# analog-in.net
KiCad netlist of a schematic drawn in EAGLE
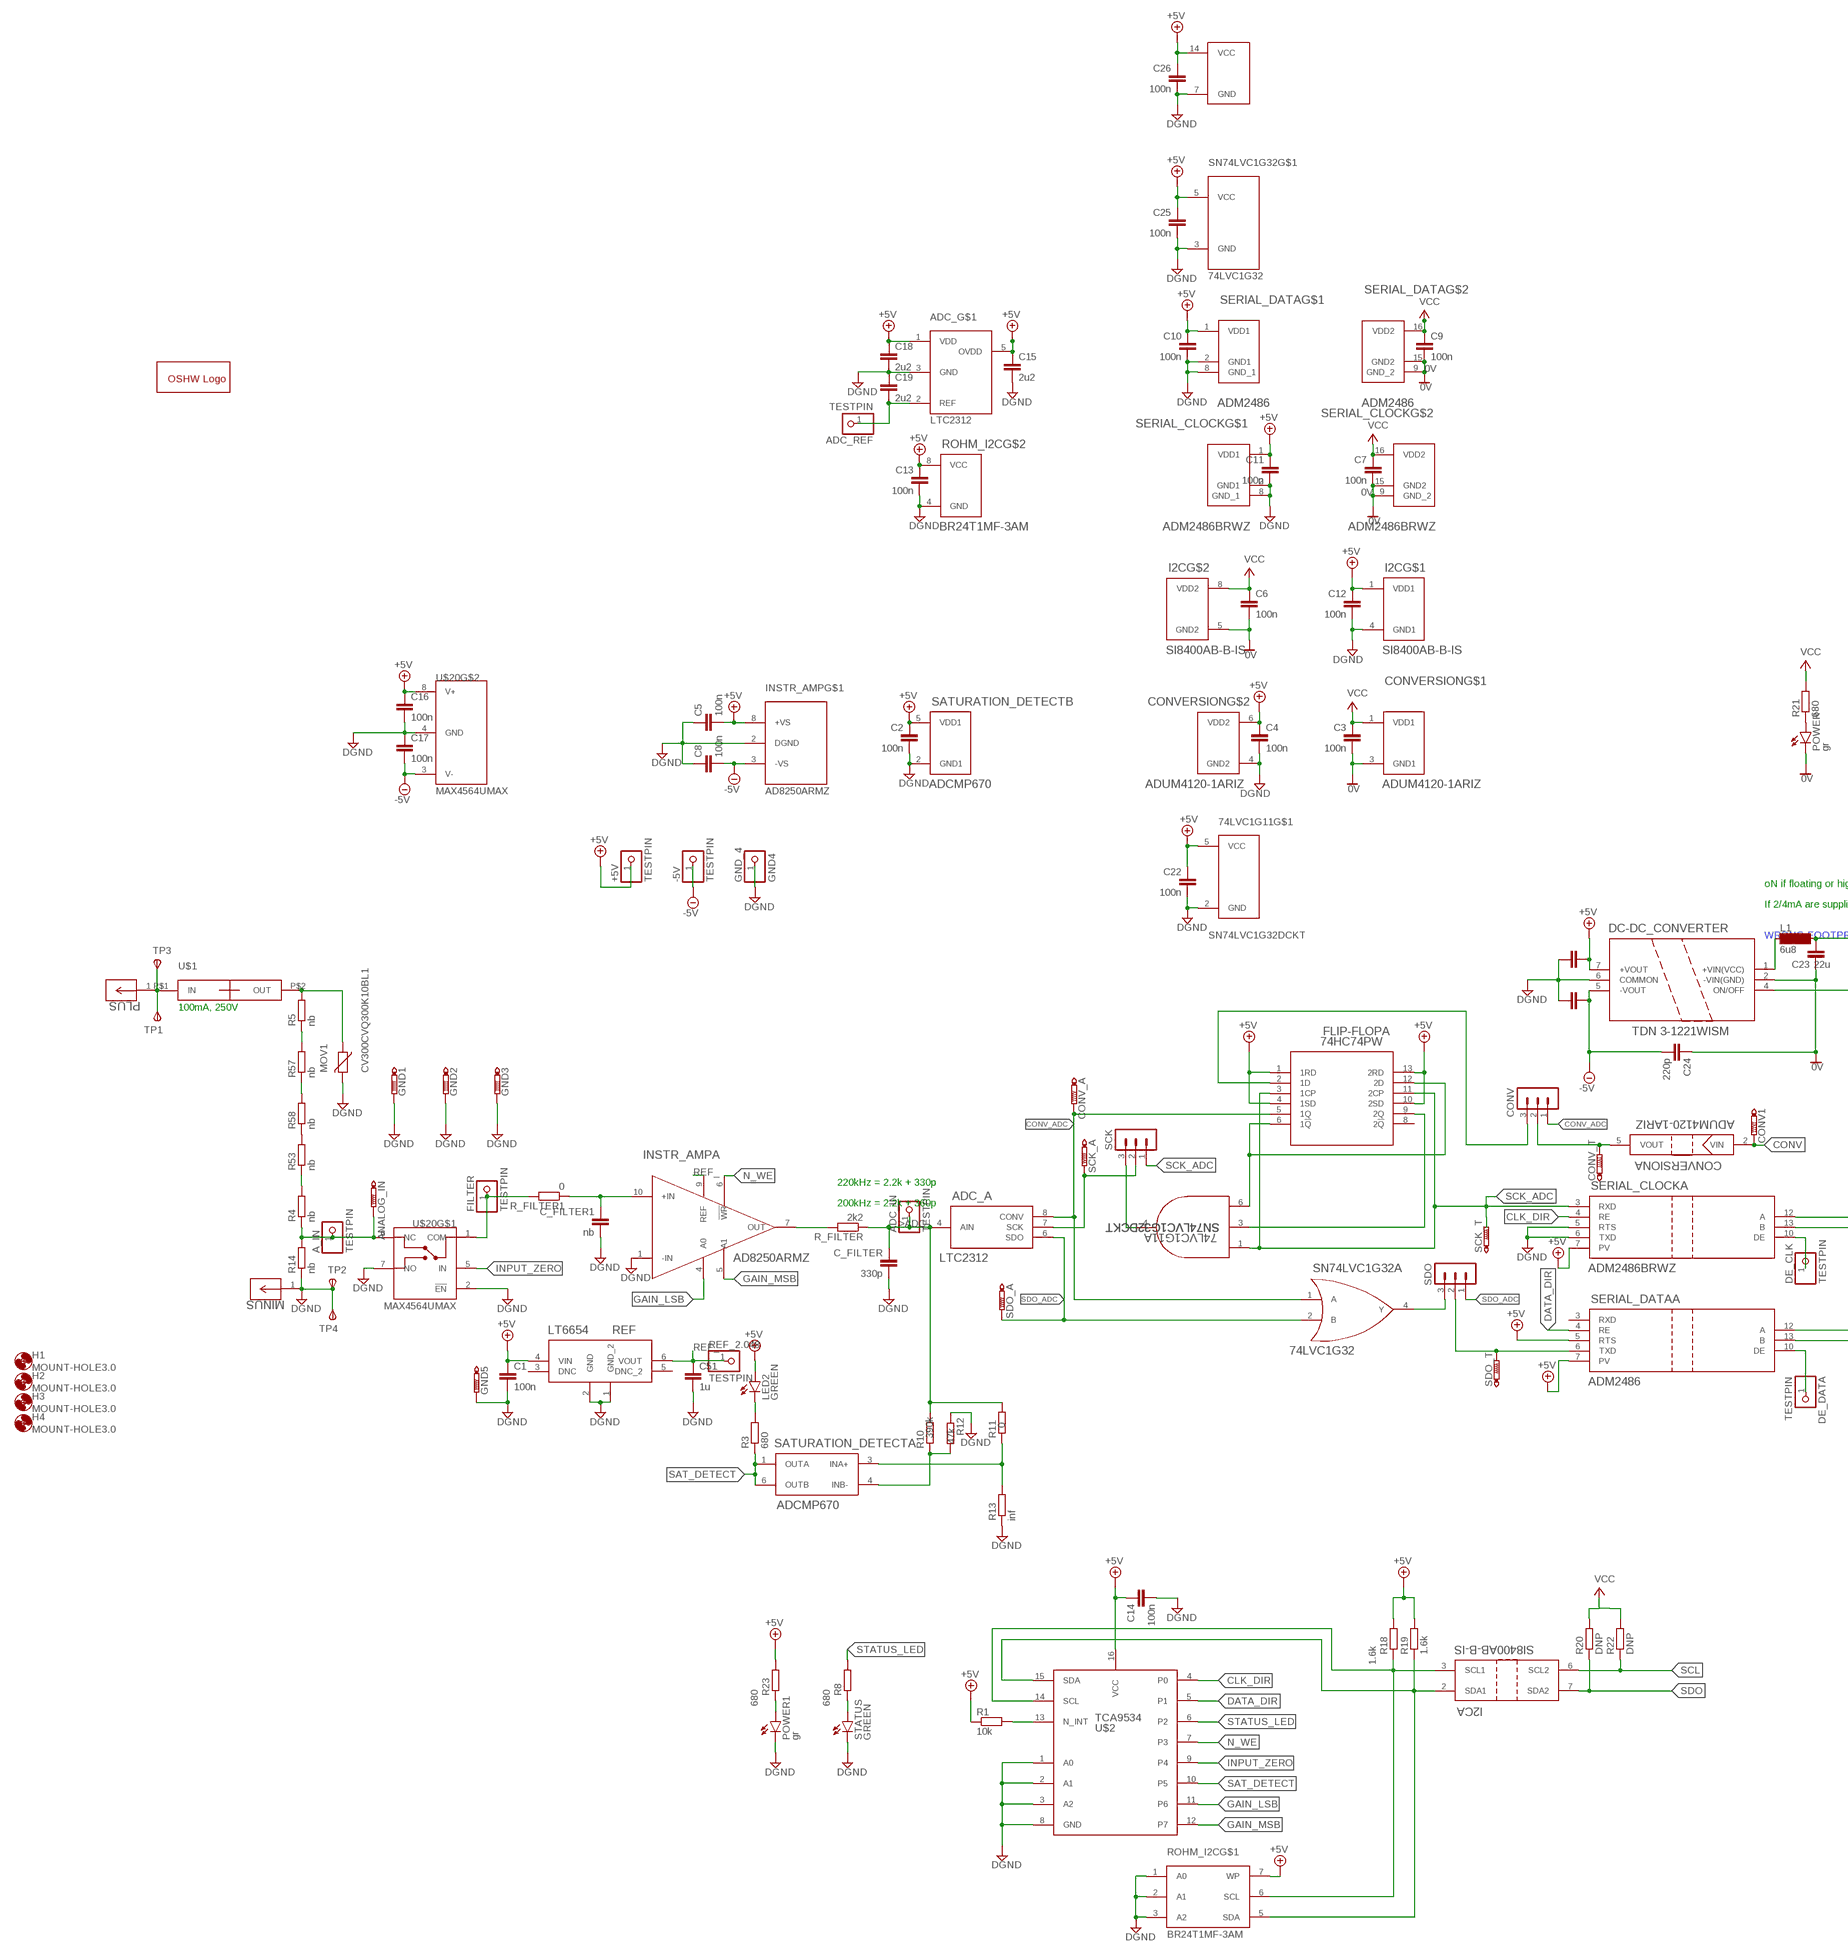
[diagram p0: schematic, sheet 1, part 1 of 2]
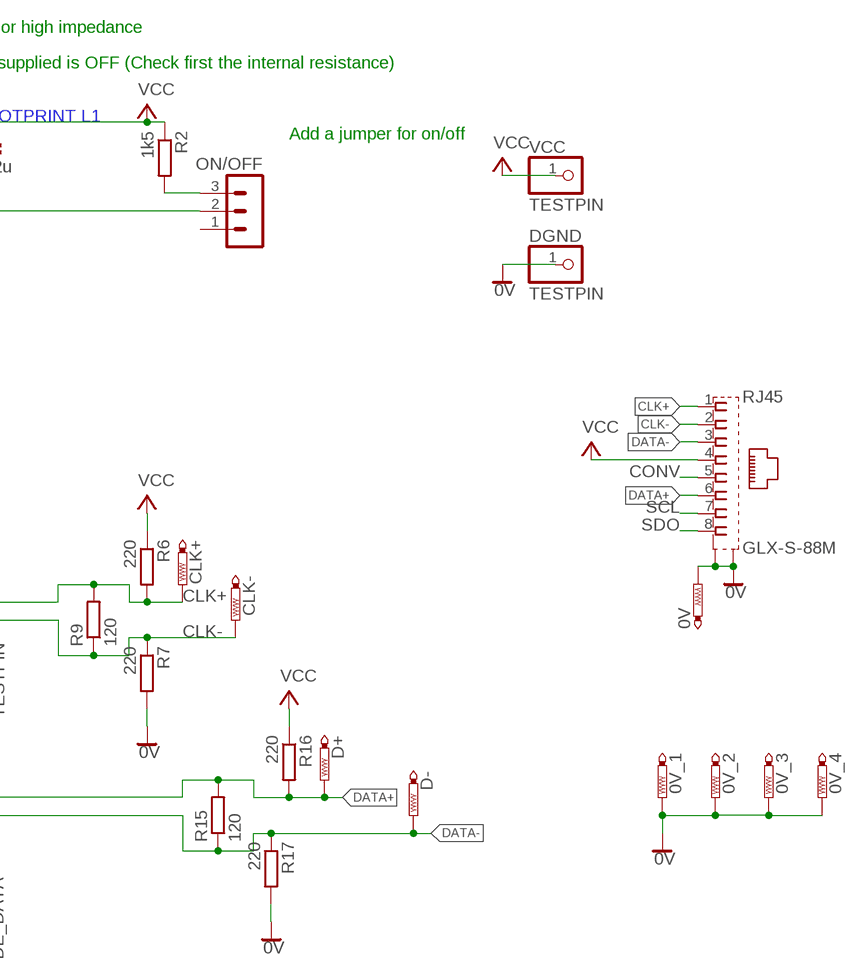
[diagram p1: schematic, sheet 1, part 2 of 2]

(export (version "E")
  (design (tool "Eeschema 10.0.6"))
  (components
    (comp (ref "+5V")
      (value "TESTPIN")
      (footprint "eagle-import:1X01")
      (libsource (lib "eagle-import") (part "TESTPIN"))
    )
    (comp (ref "-5V")
      (value "TESTPIN")
      (footprint "eagle-import:1X01")
      (libsource (lib "eagle-import") (part "TESTPIN"))
    )
    (comp (ref "0V")
      (value "PTR1B1,27")
      (footprint "eagle-import:B1,27")
      (libsource (lib "eagle-import") (part "PTR1B1,27"))
    )
    (comp (ref "0V_1")
      (value "PTR1B1,27")
      (footprint "eagle-import:B1,27")
      (libsource (lib "eagle-import") (part "PTR1B1,27"))
    )
    (comp (ref "0V_2")
      (value "PTR1B1,27")
      (footprint "eagle-import:B1,27")
      (libsource (lib "eagle-import") (part "PTR1B1,27"))
    )
    (comp (ref "0V_3")
      (value "PTR1B1,27")
      (footprint "eagle-import:B1,27")
      (libsource (lib "eagle-import") (part "PTR1B1,27"))
    )
    (comp (ref "0V_4")
      (value "PTR1B1,27")
      (footprint "eagle-import:B1,27")
      (libsource (lib "eagle-import") (part "PTR1B1,27"))
    )
    (comp (ref "74LVC1G11")
      (value "SN74LVC1G32DCKT")
      (footprint "eagle-import:DBV0006A_L")
      (fields (field (name "MANUFACTURER") "Texas Instruments") (field (name "PARTNUMBER") "SN74LVC1G11DBVR"))
      (libsource (lib "eagle-import") (part "SN74LVC1G11DBVRDBV0006A_L"))
    )
    (comp (ref "ADC_")
      (value "LTC2312")
      (footprint "eagle-import:TSOT-23_TS8_LIT")
      (fields
        (field (name "MANUFACTURER_PART_NUMBER") "LTC2312ITS8-14#TRMPBF")
        (field (name "DIGIKEY") "LTC2312CTS8-14#TRMPBFTR-ND")
      )
      (libsource (lib "eagle-import") (part "LTC2312ITS8-14TRMPBF"))
    )
    (comp (ref "ADC_IN")
      (value "TESTPIN")
      (footprint "eagle-import:1X01")
      (libsource (lib "eagle-import") (part "TESTPIN"))
    )
    (comp (ref "ADC_REF")
      (value "TESTPIN")
      (footprint "eagle-import:1X01")
      (libsource (lib "eagle-import") (part "TESTPIN"))
    )
    (comp (ref "ANALOG_IN")
      (value "PTR1B1,27")
      (footprint "eagle-import:B1,27")
      (libsource (lib "eagle-import") (part "PTR1B1,27"))
    )
    (comp (ref "A_IN")
      (value "TESTPIN")
      (footprint "eagle-import:1X01")
      (libsource (lib "eagle-import") (part "TESTPIN"))
    )
    (comp (ref "C1")
      (value "100n")
      (footprint "eagle-import:C0805")
      (libsource (lib "eagle-import") (part "C-EUC0805"))
    )
    (comp (ref "C2")
      (value "100n")
      (footprint "eagle-import:C0805K")
      (libsource (lib "eagle-import") (part "C-EUC0805K"))
    )
    (comp (ref "C3")
      (value "100n")
      (footprint "eagle-import:C0805K")
      (libsource (lib "eagle-import") (part "C-EUC0805K"))
    )
    (comp (ref "C4")
      (value "100n")
      (footprint "eagle-import:C0805K")
      (libsource (lib "eagle-import") (part "C-EUC0805K"))
    )
    (comp (ref "C5")
      (value "100n")
      (footprint "eagle-import:C0805K")
      (libsource (lib "eagle-import") (part "C-EUC0805K"))
    )
    (comp (ref "C6")
      (value "100n")
      (footprint "eagle-import:C0805K")
      (libsource (lib "eagle-import") (part "C-EUC0805K"))
    )
    (comp (ref "C7")
      (value "100n")
      (footprint "eagle-import:C0805K")
      (libsource (lib "eagle-import") (part "C-EUC0805K"))
    )
    (comp (ref "C8")
      (value "100n")
      (footprint "eagle-import:C0805K")
      (libsource (lib "eagle-import") (part "C-EUC0805K"))
    )
    (comp (ref "C9")
      (value "100n")
      (footprint "eagle-import:C0805K")
      (libsource (lib "eagle-import") (part "C-EUC0805K"))
    )
    (comp (ref "C10")
      (value "100n")
      (footprint "eagle-import:C0805K")
      (libsource (lib "eagle-import") (part "C-EUC0805K"))
    )
    (comp (ref "C11")
      (value "100n")
      (footprint "eagle-import:C0805K")
      (libsource (lib "eagle-import") (part "C-EUC0805K"))
    )
    (comp (ref "C12")
      (value "100n")
      (footprint "eagle-import:C0805K")
      (libsource (lib "eagle-import") (part "C-EUC0805K"))
    )
    (comp (ref "C13")
      (value "100n")
      (footprint "eagle-import:C0805K")
      (libsource (lib "eagle-import") (part "C-EUC0805K"))
    )
    (comp (ref "C14")
      (value "100n")
      (footprint "eagle-import:C0805K")
      (libsource (lib "eagle-import") (part "C-EUC0805K"))
    )
    (comp (ref "C15")
      (value "2u2")
      (footprint "eagle-import:C0805K")
      (libsource (lib "eagle-import") (part "C-EUC0805K"))
    )
    (comp (ref "C16")
      (value "100n")
      (footprint "eagle-import:C0805K")
      (libsource (lib "eagle-import") (part "C-EUC0805K"))
    )
    (comp (ref "C17")
      (value "100n")
      (footprint "eagle-import:C0805K")
      (libsource (lib "eagle-import") (part "C-EUC0805K"))
    )
    (comp (ref "C18")
      (value "2u2")
      (footprint "eagle-import:C0805K")
      (libsource (lib "eagle-import") (part "C-EUC0805K"))
    )
    (comp (ref "C19")
      (value "2u2")
      (footprint "eagle-import:C0805K")
      (libsource (lib "eagle-import") (part "C-EUC0805K"))
    )
    (comp (ref "C20")
      (value "100n")
      (footprint "eagle-import:C0805K")
      (libsource (lib "eagle-import") (part "C-EUC0805K"))
    )
    (comp (ref "C21")
      (value "100n")
      (footprint "eagle-import:C0805K")
      (libsource (lib "eagle-import") (part "C-EUC0805K"))
    )
    (comp (ref "C22")
      (value "100n")
      (footprint "eagle-import:C0805K")
      (libsource (lib "eagle-import") (part "C-EUC0805K"))
    )
    (comp (ref "C23")
      (value "22u")
      (footprint "eagle-import:C1206")
      (libsource (lib "eagle-import") (part "C-EUC1206"))
    )
    (comp (ref "C24")
      (value "220p")
      (footprint "eagle-import:C1808")
      (libsource (lib "eagle-import") (part "C-EUC1808"))
    )
    (comp (ref "C25")
      (value "100n")
      (footprint "eagle-import:C0805K")
      (libsource (lib "eagle-import") (part "C-EUC0805K"))
    )
    (comp (ref "C26")
      (value "100n")
      (footprint "eagle-import:C0805K")
      (libsource (lib "eagle-import") (part "C-EUC0805K"))
    )
    (comp (ref "C51")
      (value "1u")
      (footprint "eagle-import:C0805")
      (libsource (lib "eagle-import") (part "C-EUC0805"))
    )
    (comp (ref "CLK+")
      (value "PTR1B1,27")
      (footprint "eagle-import:B1,27")
      (libsource (lib "eagle-import") (part "PTR1B1,27"))
    )
    (comp (ref "CLK-")
      (value "PTR1B1,27")
      (footprint "eagle-import:B1,27")
      (libsource (lib "eagle-import") (part "PTR1B1,27"))
    )
    (comp (ref "CONV")
      (value "MA03-1")
      (footprint "eagle-import:MA03-1")
      (libsource (lib "eagle-import") (part "MA03-1"))
    )
    (comp (ref "CONV1")
      (value "PTR1B1,27")
      (footprint "eagle-import:B1,27")
      (libsource (lib "eagle-import") (part "PTR1B1,27"))
    )
    (comp (ref "CONVERSION")
      (value "ADUM4120-1ARIZ")
      (footprint "eagle-import:RI_6_1_ADI")
      (fields (field (name "DIGIKEY") "ADUM4120-1ARIZ-ND"))
      (libsource (lib "eagle-import") (part "ADUM4120-1ARIZ"))
    )
    (comp (ref "CONV_A")
      (value "PTR1B1,27")
      (footprint "eagle-import:B1,27")
      (libsource (lib "eagle-import") (part "PTR1B1,27"))
    )
    (comp (ref "CONV_T")
      (value "PTR1B1,27")
      (footprint "eagle-import:B1,27")
      (libsource (lib "eagle-import") (part "PTR1B1,27"))
    )
    (comp (ref "C_FILTER")
      (value "330p")
      (footprint "eagle-import:C0805K")
      (libsource (lib "eagle-import") (part "C-EUC0805K"))
    )
    (comp (ref "C_FILTER1")
      (value "nb")
      (footprint "eagle-import:C0805K")
      (libsource (lib "eagle-import") (part "C-EUC0805K"))
    )
    (comp (ref "D+")
      (value "PTR1B1,27")
      (footprint "eagle-import:B1,27")
      (libsource (lib "eagle-import") (part "PTR1B1,27"))
    )
    (comp (ref "D-")
      (value "PTR1B1,27")
      (footprint "eagle-import:B1,27")
      (libsource (lib "eagle-import") (part "PTR1B1,27"))
    )
    (comp (ref "DC-DC_CONVERTER")
      (value "TDN 3-1221WISM")
      (footprint "eagle-import:TDN3_TRP")
      (fields
        (field (name "MANUFACTURER_PART_NUMBER") "TDN 3-1211WI")
        (field (name "MANUFACTURER_PART_NUMBER_1") "TDN 3-1221WISM")
        (field (name "COPYRIGHT") "Copyright (C) 2018 Accelerated Designs. All rights reserved")
      )
      (libsource (lib "eagle-import") (part "TDN_3-1211WI"))
    )
    (comp (ref "DE_CLK")
      (value "TESTPIN")
      (footprint "eagle-import:1X01")
      (libsource (lib "eagle-import") (part "TESTPIN"))
    )
    (comp (ref "DE_DATA")
      (value "TESTPIN")
      (footprint "eagle-import:1X01")
      (libsource (lib "eagle-import") (part "TESTPIN"))
    )
    (comp (ref "DGND")
      (value "TESTPIN")
      (footprint "eagle-import:1X01")
      (libsource (lib "eagle-import") (part "TESTPIN"))
    )
    (comp (ref "FILTER")
      (value "TESTPIN")
      (footprint "eagle-import:1X01")
      (libsource (lib "eagle-import") (part "TESTPIN"))
    )
    (comp (ref "FLIP-FLOP")
      (value "74HC74PW")
      (footprint "eagle-import:TSSOP14_SOT402-1_NEX")
      (fields
        (field (name "MANUFACTURER_PART_NUMBER") "74HC74PW-Q100,118")
        (field (name "DIGIKEY") "1727-4083-1-ND")
        (field (name "COPYRIGHT") "Copyright (C) 2018 Accelerated Designs. All rights reserved")
      )
      (libsource (lib "eagle-import") (part "74HC74PW-Q100,118"))
    )
    (comp (ref "GND1")
      (value "PTR1B1,27")
      (footprint "eagle-import:B1,27")
      (libsource (lib "eagle-import") (part "PTR1B1,27"))
    )
    (comp (ref "GND2")
      (value "PTR1B1,27")
      (footprint "eagle-import:B1,27")
      (libsource (lib "eagle-import") (part "PTR1B1,27"))
    )
    (comp (ref "GND3")
      (value "PTR1B1,27")
      (footprint "eagle-import:B1,27")
      (libsource (lib "eagle-import") (part "PTR1B1,27"))
    )
    (comp (ref "GND5")
      (value "PTR1B1,27")
      (footprint "eagle-import:B1,27")
      (libsource (lib "eagle-import") (part "PTR1B1,27"))
    )
    (comp (ref "GND_4")
      (value "GND4")
      (footprint "eagle-import:1X01")
      (libsource (lib "eagle-import") (part "TESTPIN"))
    )
    (comp (ref "GOLD_ORB_SM1")
      (value "OSHWLOGOLOGO8MM")
      (footprint "eagle-import:OSHW_8MM")
      (libsource (lib "eagle-import") (part "OSHWLOGOLOGO8MM"))
    )
    (comp (ref "H1")
      (value "MOUNT-HOLE3.0")
      (footprint "eagle-import:3,0")
      (libsource (lib "eagle-import") (part "MOUNT-HOLE3.0"))
    )
    (comp (ref "H2")
      (value "MOUNT-HOLE3.0")
      (footprint "eagle-import:3,0")
      (libsource (lib "eagle-import") (part "MOUNT-HOLE3.0"))
    )
    (comp (ref "H3")
      (value "MOUNT-HOLE3.0")
      (footprint "eagle-import:3,0")
      (libsource (lib "eagle-import") (part "MOUNT-HOLE3.0"))
    )
    (comp (ref "H4")
      (value "MOUNT-HOLE3.0")
      (footprint "eagle-import:3,0")
      (libsource (lib "eagle-import") (part "MOUNT-HOLE3.0"))
    )
    (comp (ref "I2C")
      (value "SI8400AB-B-IS")
      (footprint "eagle-import:R_8_ADI")
      (fields
        (field (name "MANUFACTURER_PART_NUMBER") "ADUM1251WARZ")
        (field (name "DIGIKEY") "ADUM1251ARZ-RL7TR-ND")
        (field (name "COPYRIGHT") "Copyright (C) 2018 Accelerated Designs. All rights reserved")
      )
      (libsource (lib "eagle-import") (part "ADUM1251WARZ"))
    )
    (comp (ref "INSTR_AMP")
      (value "AD8250ARMZ")
      (footprint "eagle-import:RM_10_ADI")
      (fields (field (name "DIGIKEY") "AD8250ARMZ-R7TR-ND"))
      (libsource (lib "eagle-import") (part "AD8250ARMZ"))
    )
    (comp (ref "L1")
      (value "6u8")
      (footprint "eagle-import:SM-NE29")
      (libsource (lib "eagle-import") (part "SM-NE29"))
    )
    (comp (ref "LED2")
      (value "GREEN")
      (footprint "eagle-import:SML0805")
      (libsource (lib "eagle-import") (part "LEDSML0805"))
    )
    (comp (ref "MINUS")
      (value "23.3200-21")
      (footprint "eagle-import:CONN_23.3200-21_SBI")
      (fields (field (name "COPYRIGHT") "Copyright (C) 2018 Accelerated Designs. All rights reserved"))
      (libsource (lib "eagle-import") (part "23.3200-21"))
    )
    (comp (ref "MOV1")
      (value "CV300CVQ300K10BL1")
      (footprint "eagle-import:CVQ300K10")
      (libsource (lib "eagle-import") (part "CV300CVQ300K10BL1"))
    )
    (comp (ref "ON/OFF")
      (value "MA03-1")
      (footprint "eagle-import:MA03-1")
      (libsource (lib "eagle-import") (part "MA03-1"))
    )
    (comp (ref "PLUS")
      (value "23.3200-21")
      (footprint "eagle-import:CONN_23.3200-21_SBI")
      (fields (field (name "COPYRIGHT") "Copyright (C) 2018 Accelerated Designs. All rights reserved"))
      (libsource (lib "eagle-import") (part "23.3200-21"))
    )
    (comp (ref "POWER")
      (value "gr")
      (footprint "eagle-import:SML0805")
      (libsource (lib "eagle-import") (part "LEDSML0805"))
    )
    (comp (ref "POWER1")
      (value "gr")
      (footprint "eagle-import:SML0805")
      (libsource (lib "eagle-import") (part "LEDSML0805"))
    )
    (comp (ref "R1")
      (value "10k")
      (footprint "eagle-import:R0805")
      (libsource (lib "eagle-import") (part "R-EU_R0805"))
    )
    (comp (ref "R2")
      (value "1k5")
      (footprint "eagle-import:R0805")
      (libsource (lib "eagle-import") (part "R-EU_R0805"))
    )
    (comp (ref "R3")
      (value "680")
      (footprint "eagle-import:R0805")
      (libsource (lib "eagle-import") (part "R-EU_R0805"))
    )
    (comp (ref "R4")
      (value "nb")
      (footprint "eagle-import:R1206")
      (libsource (lib "eagle-import") (part "R-EU_R1206"))
    )
    (comp (ref "R5")
      (value "nb")
      (footprint "eagle-import:R1206")
      (libsource (lib "eagle-import") (part "R-EU_R1206"))
    )
    (comp (ref "R6")
      (value "220")
      (footprint "eagle-import:R0805")
      (libsource (lib "eagle-import") (part "R-EU_R0805"))
    )
    (comp (ref "R7")
      (value "220")
      (footprint "eagle-import:R0805")
      (libsource (lib "eagle-import") (part "R-EU_R0805"))
    )
    (comp (ref "R8")
      (value "680")
      (footprint "eagle-import:R0805")
      (libsource (lib "eagle-import") (part "resistor_348_R-EU_R0805"))
    )
    (comp (ref "R9")
      (value "120")
      (footprint "eagle-import:R0805")
      (libsource (lib "eagle-import") (part "R-EU_R0805"))
    )
    (comp (ref "R10")
      (value "390k")
      (footprint "eagle-import:R0805")
      (libsource (lib "eagle-import") (part "R-EU_R0805"))
    )
    (comp (ref "R11")
      (value "0")
      (footprint "eagle-import:R0805")
      (libsource (lib "eagle-import") (part "R-EU_R0805"))
    )
    (comp (ref "R12")
      (value "47k")
      (footprint "eagle-import:R0805")
      (libsource (lib "eagle-import") (part "R-EU_R0805"))
    )
    (comp (ref "R13")
      (value "inf")
      (footprint "eagle-import:R0805")
      (libsource (lib "eagle-import") (part "R-EU_R0805"))
    )
    (comp (ref "R14")
      (value "nb")
      (footprint "eagle-import:R0805")
      (libsource (lib "eagle-import") (part "R-EU_R0805"))
    )
    (comp (ref "R15")
      (value "120")
      (footprint "eagle-import:R0805")
      (libsource (lib "eagle-import") (part "R-EU_R0805"))
    )
    (comp (ref "R16")
      (value "220")
      (footprint "eagle-import:R0805")
      (libsource (lib "eagle-import") (part "R-EU_R0805"))
    )
    (comp (ref "R17")
      (value "220")
      (footprint "eagle-import:R0805")
      (libsource (lib "eagle-import") (part "R-EU_R0805"))
    )
    (comp (ref "R18")
      (value "1.6k")
      (footprint "eagle-import:R0805")
      (libsource (lib "eagle-import") (part "resistor_348_R-EU_R0805"))
    )
    (comp (ref "R19")
      (value "1.6k")
      (footprint "eagle-import:R0805")
      (libsource (lib "eagle-import") (part "resistor_348_R-EU_R0805"))
    )
    (comp (ref "R20")
      (value "DNP")
      (footprint "eagle-import:R0805")
      (libsource (lib "eagle-import") (part "resistor_348_R-EU_R0805"))
    )
    (comp (ref "R21")
      (value "680")
      (footprint "eagle-import:R0805")
      (libsource (lib "eagle-import") (part "R-EU_R0805"))
    )
    (comp (ref "R22")
      (value "DNP")
      (footprint "eagle-import:R0805")
      (libsource (lib "eagle-import") (part "resistor_348_R-EU_R0805"))
    )
    (comp (ref "R23")
      (value "680")
      (footprint "eagle-import:R0805")
      (libsource (lib "eagle-import") (part "resistor_348_R-EU_R0805"))
    )
    (comp (ref "R53")
      (value "nb")
      (footprint "eagle-import:R1206")
      (libsource (lib "eagle-import") (part "R-EU_R1206"))
    )
    (comp (ref "R57")
      (value "nb")
      (footprint "eagle-import:R1206")
      (libsource (lib "eagle-import") (part "R-EU_R1206"))
    )
    (comp (ref "R58")
      (value "nb")
      (footprint "eagle-import:R1206")
      (libsource (lib "eagle-import") (part "R-EU_R1206"))
    )
    (comp (ref "REF")
      (value "LT6654")
      (footprint "eagle-import:S_6_ADI")
      (fields
        (field (name "MANUFACTURER_PART_NUMBER") "LT6654AIS6-2.048#TRMPBF")
        (field (name "COPYRIGHT") "Copyright (C) 2016 Accelerated Designs. All rights reserved")
      )
      (libsource (lib "eagle-import") (part "LT6654AIS6-2.048TRMPBF"))
    )
    (comp (ref "REF_2.048")
      (value "TESTPIN")
      (footprint "eagle-import:1X01")
      (libsource (lib "eagle-import") (part "TESTPIN"))
    )
    (comp (ref "RJ45")
      (value "GLX-S-88M")
      (footprint "eagle-import:GLX-S-88M")
      (libsource (lib "eagle-import") (part "GLX-S-88M"))
    )
    (comp (ref "ROHM_I2C")
      (value "BR24T1MF-3AM")
      (footprint "eagle-import:BR24T1MFJ-3AM")
      (fields (field (name "DIGIKEY") "BR24T1MF-3AME2TR-ND"))
      (libsource (lib "eagle-import") (part "BR24T1MF-3AM"))
    )
    (comp (ref "R_FILTER")
      (value "2k2")
      (footprint "eagle-import:R0805")
      (libsource (lib "eagle-import") (part "R-EU_R0805"))
    )
    (comp (ref "R_FILTER1")
      (value "0")
      (footprint "eagle-import:R0805")
      (libsource (lib "eagle-import") (part "R-EU_R0805"))
    )
    (comp (ref "SATURATION_DETECT")
      (value "ADCMP670")
      (footprint "eagle-import:UJ_6_ADI")
      (fields
        (field (name "MANUFACTURER_PART_NUMBER") "ADCMP670-1YUJZ-RL7")
        (field (name "DIGIKEY") "ADCMP670-1YUJZ-RL7TR-ND")
      )
      (libsource (lib "eagle-import") (part "ADCMP670-1YUJZ-RL7"))
    )
    (comp (ref "SCK")
      (value "MA03-1")
      (footprint "eagle-import:MA03-1")
      (libsource (lib "eagle-import") (part "MA03-1"))
    )
    (comp (ref "SCK_A")
      (value "PTR1B1,27")
      (footprint "eagle-import:B1,27")
      (libsource (lib "eagle-import") (part "PTR1B1,27"))
    )
    (comp (ref "SCK_T")
      (value "PTR1B1,27")
      (footprint "eagle-import:B1,27")
      (libsource (lib "eagle-import") (part "PTR1B1,27"))
    )
    (comp (ref "SDO")
      (value "MA03-1")
      (footprint "eagle-import:MA03-1")
      (libsource (lib "eagle-import") (part "MA03-1"))
    )
    (comp (ref "SDO_A")
      (value "PTR1B1,27")
      (footprint "eagle-import:B1,27")
      (libsource (lib "eagle-import") (part "PTR1B1,27"))
    )
    (comp (ref "SDO_T")
      (value "PTR1B1,27")
      (footprint "eagle-import:B1,27")
      (libsource (lib "eagle-import") (part "PTR1B1,27"))
    )
    (comp (ref "SERIAL_CLOCK")
      (value "ADM2486BRWZ")
      (footprint "eagle-import:RW_16_ADI")
      (fields
        (field (name "MANUFACTURER_PART_NUMBER") "ADM2486BRWZ-REEL")
        (field (name "DIGIKEY") "ADM2486BRWZ-REELTR-ND")
      )
      (libsource (lib "eagle-import") (part "ADM2486BRWZ-REEL"))
    )
    (comp (ref "SERIAL_DATA")
      (value "ADM2486")
      (footprint "eagle-import:RW_16_ADI")
      (fields
        (field (name "MANUFACTURER_PART_NUMBER") "ADM2486BRWZ-REEL")
        (field (name "DIGIKEY") "ADM2486BRWZ-REELTR-ND")
      )
      (libsource (lib "eagle-import") (part "ADM2486BRWZ-REEL"))
    )
    (comp (ref "SN74LVC1G32")
      (value "74LVC1G32")
      (footprint "eagle-import:DCK5-M")
      (fields
        (field (name "GENERIC_PART_NUMBER") "SN74LVC1G32")
        (field (name "MANUFACTURER") "Texas Instruments")
        (field (name "MANUFACTURER_PART_NUMBER") "SN74LVC1G32DCKT")
      )
      (libsource (lib "eagle-import") (part "SN74LVC1G32DCKTDCK5-M"))
    )
    (comp (ref "STATUS")
      (value "GREEN")
      (footprint "eagle-import:CHIPLED_0805")
      (libsource (lib "eagle-import") (part "LEDCHIPLED_0805"))
    )
    (comp (ref "TP1")
      (value "TPSTP20SQ")
      (footprint "eagle-import:TP20SQ")
      (libsource (lib "eagle-import") (part "TPSTP20SQ"))
    )
    (comp (ref "TP2")
      (value "TPSTP20SQ")
      (footprint "eagle-import:TP20SQ")
      (libsource (lib "eagle-import") (part "TPSTP20SQ"))
    )
    (comp (ref "TP3")
      (value "TPSTP20SQ")
      (footprint "eagle-import:TP20SQ")
      (libsource (lib "eagle-import") (part "TPSTP20SQ"))
    )
    (comp (ref "TP4")
      (value "TPSTP20SQ")
      (footprint "eagle-import:TP20SQ")
      (libsource (lib "eagle-import") (part "TPSTP20SQ"))
    )
    (comp (ref "U$1")
      (value "0508.500MXEP")
      (footprint "eagle-import:0508.500MXEP")
      (libsource (lib "eagle-import") (part "0508.500MXEP"))
    )
    (comp (ref "U$2")
      (value "TCA9534")
      (footprint "eagle-import:TSSOP16L")
      (libsource (lib "eagle-import") (part "TCA9534"))
    )
    (comp (ref "U$20")
      (value "MAX4564UMAX")
      (footprint "eagle-import:UMAX8")
      (fields (field (name "DIGIKEY") "MAX4564EUA+TR-ND") (field (name "MOUSER") "700-MAX4564EUA "))
      (libsource (lib "eagle-import") (part "MAX4564UMAX"))
    )
    (comp (ref "VCC")
      (value "TESTPIN")
      (footprint "eagle-import:1X01")
      (libsource (lib "eagle-import") (part "TESTPIN"))
    )
  )
  (nets
    (net (code "1") (name "+5V") (class "Default")
      (node (ref "+5V") (pin "1") (pinfunction "1_1") (pintype "passive"))
      (node (ref "74LVC1G11") (pin "5") (pinfunction "VCC_5") (pintype "bidirectional"))
      (node (ref "ADC_") (pin "1") (pinfunction "VDD_1") (pintype "bidirectional"))
      (node (ref "ADC_") (pin "5") (pinfunction "OVDD_5") (pintype "bidirectional"))
      (node (ref "C1") (pin "1") (pinfunction "1_1") (pintype "passive"))
      (node (ref "C10") (pin "1") (pinfunction "1_1") (pintype "passive"))
      (node (ref "C11") (pin "1") (pinfunction "1_1") (pintype "passive"))
      (node (ref "C12") (pin "1") (pinfunction "1_1") (pintype "passive"))
      (node (ref "C13") (pin "1") (pinfunction "1_1") (pintype "passive"))
      (node (ref "C14") (pin "1") (pinfunction "1_1") (pintype "passive"))
      (node (ref "C15") (pin "1") (pinfunction "1_1") (pintype "passive"))
      (node (ref "C16") (pin "1") (pinfunction "1_1") (pintype "passive"))
      (node (ref "C18") (pin "1") (pinfunction "1_1") (pintype "passive"))
      (node (ref "C2") (pin "1") (pinfunction "1_1") (pintype "passive"))
      (node (ref "C20") (pin "2") (pinfunction "2_2") (pintype "passive"))
      (node (ref "C22") (pin "1") (pinfunction "1_1") (pintype "passive"))
      (node (ref "C25") (pin "1") (pinfunction "1_1") (pintype "passive"))
      (node (ref "C26") (pin "1") (pinfunction "1_1") (pintype "passive"))
      (node (ref "C4") (pin "1") (pinfunction "1_1") (pintype "passive"))
      (node (ref "C5") (pin "2") (pinfunction "2_2") (pintype "passive"))
      (node (ref "CONVERSION") (pin "6") (pinfunction "VDD2_6") (pintype "passive"))
      (node (ref "DC-DC_CONVERTER") (pin "7") (pinfunction "+VOUT_7") (pintype "output"))
      (node (ref "FLIP-FLOP") (pin "1") (pinfunction "1RD_1") (pintype "input"))
      (node (ref "FLIP-FLOP") (pin "10") (pinfunction "2SD_10") (pintype "input"))
      (node (ref "FLIP-FLOP") (pin "13") (pinfunction "2RD_13") (pintype "input"))
      (node (ref "FLIP-FLOP") (pin "14") (pinfunction "VCC_14") (pintype "power_in"))
      (node (ref "FLIP-FLOP") (pin "4") (pinfunction "1SD_4") (pintype "input"))
      (node (ref "I2C") (pin "1") (pinfunction "VDD1_1") (pintype "power_in"))
      (node (ref "INSTR_AMP") (pin "8") (pinfunction "+VS_8") (pintype "bidirectional"))
      (node (ref "LED2") (pin "A") (pinfunction "A_A") (pintype "passive"))
      (node (ref "R1") (pin "1") (pinfunction "1_1") (pintype "passive"))
      (node (ref "R18") (pin "2") (pinfunction "2_2") (pintype "passive"))
      (node (ref "R19") (pin "2") (pinfunction "2_2") (pintype "passive"))
      (node (ref "R23") (pin "2") (pinfunction "2_2") (pintype "passive"))
      (node (ref "REF") (pin "4") (pinfunction "VIN_4") (pintype "input"))
      (node (ref "ROHM_I2C") (pin "7") (pinfunction "WP_7") (pintype "input"))
      (node (ref "ROHM_I2C") (pin "8") (pinfunction "VCC_8") (pintype "passive"))
      (node (ref "SATURATION_DETECT") (pin "5") (pinfunction "VDD1_5") (pintype "passive"))
      (node (ref "SERIAL_CLOCK") (pin "1") (pinfunction "VDD1_1") (pintype "power_in"))
      (node (ref "SERIAL_CLOCK") (pin "7") (pinfunction "PV_7") (pintype "passive"))
      (node (ref "SERIAL_DATA") (pin "1") (pinfunction "VDD1_1") (pintype "power_in"))
      (node (ref "SERIAL_DATA") (pin "5") (pinfunction "RTS_5") (pintype "passive"))
      (node (ref "SERIAL_DATA") (pin "7") (pinfunction "PV_7") (pintype "passive"))
      (node (ref "SN74LVC1G32") (pin "5") (pinfunction "VCC_5") (pintype "bidirectional"))
      (node (ref "U$2") (pin "16") (pinfunction "VCC_16") (pintype "bidirectional"))
      (node (ref "U$20") (pin "8") (pinfunction "V+_8") (pintype "bidirectional"))
    )
    (net (code "2") (name "-5V") (class "Default")
      (node (ref "-5V") (pin "1") (pinfunction "1_1") (pintype "passive"))
      (node (ref "C17") (pin "2") (pinfunction "2_2") (pintype "passive"))
      (node (ref "C21") (pin "2") (pinfunction "2_2") (pintype "passive"))
      (node (ref "C24") (pin "2") (pinfunction "2_2") (pintype "passive"))
      (node (ref "C8") (pin "2") (pinfunction "2_2") (pintype "passive"))
      (node (ref "DC-DC_CONVERTER") (pin "5") (pinfunction "-VOUT_5") (pintype "output"))
      (node (ref "INSTR_AMP") (pin "3") (pinfunction "-VS_3") (pintype "bidirectional"))
      (node (ref "U$20") (pin "3") (pinfunction "V-_3") (pintype "bidirectional"))
    )
    (net (code "3") (name "/>ADC") (class "Default")
      (node (ref "ADC_") (pin "4") (pinfunction "AIN_4") (pintype "input"))
      (node (ref "ADC_IN") (pin "1") (pinfunction "1_1") (pintype "passive"))
      (node (ref "C_FILTER") (pin "1") (pinfunction "1_1") (pintype "passive"))
      (node (ref "R10") (pin "2") (pinfunction "2_2") (pintype "passive"))
      (node (ref "R11") (pin "2") (pinfunction "2_2") (pintype "passive"))
      (node (ref "R_FILTER") (pin "1") (pinfunction "1_1") (pintype "passive"))
    )
    (net (code "4") (name "/REF_") (class "Default")
      (node (ref "C51") (pin "1") (pinfunction "1_1") (pintype "passive"))
      (node (ref "INSTR_AMP") (pin "9") (pinfunction "REF_9") (pintype "passive"))
      (node (ref "REF") (pin "6") (pinfunction "VOUT_6") (pintype "output"))
      (node (ref "REF_2.048") (pin "1") (pinfunction "1_1") (pintype "passive"))
    )
    (net (code "5") (name "0V") (class "Default")
      (node (ref "0V") (pin "TP") (pinfunction "TP_TP") (pintype "input"))
      (node (ref "0V_1") (pin "TP") (pinfunction "TP_TP") (pintype "input"))
      (node (ref "0V_2") (pin "TP") (pinfunction "TP_TP") (pintype "input"))
      (node (ref "0V_3") (pin "TP") (pinfunction "TP_TP") (pintype "input"))
      (node (ref "0V_4") (pin "TP") (pinfunction "TP_TP") (pintype "input"))
      (node (ref "C23") (pin "1") (pinfunction "1_1") (pintype "passive"))
      (node (ref "C24") (pin "1") (pinfunction "1_1") (pintype "passive"))
      (node (ref "C3") (pin "2") (pinfunction "2_2") (pintype "passive"))
      (node (ref "C6") (pin "2") (pinfunction "2_2") (pintype "passive"))
      (node (ref "C7") (pin "2") (pinfunction "2_2") (pintype "passive"))
      (node (ref "C9") (pin "2") (pinfunction "2_2") (pintype "passive"))
      (node (ref "CONVERSION") (pin "3") (pinfunction "GND1_3") (pintype "passive"))
      (node (ref "DC-DC_CONVERTER") (pin "2") (pinfunction "-VIN(GND)_2") (pintype "passive"))
      (node (ref "DGND") (pin "1") (pinfunction "1_1") (pintype "passive"))
      (node (ref "I2C") (pin "5") (pinfunction "GND2_5") (pintype "passive"))
      (node (ref "POWER") (pin "C") (pinfunction "C_C") (pintype "passive"))
      (node (ref "R17") (pin "2") (pinfunction "2_2") (pintype "passive"))
      (node (ref "R7") (pin "2") (pinfunction "2_2") (pintype "passive"))
      (node (ref "RJ45") (pin "S1") (pinfunction "S1_S1") (pintype "passive"))
      (node (ref "RJ45") (pin "S2") (pinfunction "S2_S2") (pintype "passive"))
      (node (ref "SERIAL_CLOCK") (pin "15") (pinfunction "GND2_15") (pintype "power_in"))
      (node (ref "SERIAL_CLOCK") (pin "9") (pinfunction "GND_2_9") (pintype "power_in"))
      (node (ref "SERIAL_DATA") (pin "15") (pinfunction "GND2_15") (pintype "power_in"))
      (node (ref "SERIAL_DATA") (pin "9") (pinfunction "GND_2_9") (pintype "power_in"))
    )
    (net (code "6") (name "CLK+") (class "Default")
      (node (ref "CLK+") (pin "TP") (pinfunction "TP_TP") (pintype "input"))
      (node (ref "R6") (pin "2") (pinfunction "2_2") (pintype "passive"))
      (node (ref "R9") (pin "2") (pinfunction "2_2") (pintype "passive"))
      (node (ref "RJ45") (pin "1") (pinfunction "1_1") (pintype "passive"))
      (node (ref "SERIAL_CLOCK") (pin "12") (pinfunction "A_12") (pintype "passive"))
    )
    (net (code "7") (name "CLK-") (class "Default")
      (node (ref "CLK-") (pin "TP") (pinfunction "TP_TP") (pintype "input"))
      (node (ref "R7") (pin "1") (pinfunction "1_1") (pintype "passive"))
      (node (ref "R9") (pin "1") (pinfunction "1_1") (pintype "passive"))
      (node (ref "RJ45") (pin "2") (pinfunction "2_2") (pintype "passive"))
      (node (ref "SERIAL_CLOCK") (pin "13") (pinfunction "B_13") (pintype "passive"))
    )
    (net (code "8") (name "CLK_DIR") (class "Default")
      (node (ref "SERIAL_CLOCK") (pin "4") (pinfunction "RE_4") (pintype "passive"))
      (node (ref "U$2") (pin "4") (pinfunction "P0_4") (pintype "bidirectional"))
    )
    (net (code "9") (name "CONV") (class "Default")
      (node (ref "CONV1") (pin "TP") (pinfunction "TP_TP") (pintype "input"))
      (node (ref "CONVERSION") (pin "2") (pinfunction "VIN_2") (pintype "input"))
      (node (ref "RJ45") (pin "5") (pinfunction "5_5") (pintype "passive"))
    )
    (net (code "10") (name "CONV_ADC") (class "Default")
      (node (ref "ADC_") (pin "8") (pinfunction "CONV_8") (pintype "input"))
      (node (ref "CONV") (pin "1") (pinfunction "1_1") (pintype "passive"))
      (node (ref "CONV_A") (pin "TP") (pinfunction "TP_TP") (pintype "input"))
      (node (ref "FLIP-FLOP") (pin "5") (pinfunction "1Q_5") (pintype "output"))
      (node (ref "SN74LVC1G32") (pin "1") (pinfunction "A_1") (pintype "input"))
    )
    (net (code "11") (name "DATA+") (class "Default")
      (node (ref "D+") (pin "TP") (pinfunction "TP_TP") (pintype "input"))
      (node (ref "R15") (pin "2") (pinfunction "2_2") (pintype "passive"))
      (node (ref "R16") (pin "2") (pinfunction "2_2") (pintype "passive"))
      (node (ref "RJ45") (pin "6") (pinfunction "6_6") (pintype "passive"))
      (node (ref "SERIAL_DATA") (pin "12") (pinfunction "A_12") (pintype "passive"))
    )
    (net (code "12") (name "DATA-") (class "Default")
      (node (ref "D-") (pin "TP") (pinfunction "TP_TP") (pintype "input"))
      (node (ref "R15") (pin "1") (pinfunction "1_1") (pintype "passive"))
      (node (ref "R17") (pin "1") (pinfunction "1_1") (pintype "passive"))
      (node (ref "RJ45") (pin "3") (pinfunction "3_3") (pintype "passive"))
      (node (ref "SERIAL_DATA") (pin "13") (pinfunction "B_13") (pintype "passive"))
    )
    (net (code "13") (name "DATA_DIR") (class "Default")
      (node (ref "SERIAL_DATA") (pin "4") (pinfunction "RE_4") (pintype "passive"))
      (node (ref "U$2") (pin "5") (pinfunction "P1_5") (pintype "bidirectional"))
    )
    (net (code "14") (name "DGND") (class "Default")
      (node (ref "74LVC1G11") (pin "2") (pinfunction "GND_2") (pintype "bidirectional"))
      (node (ref "ADC_") (pin "3") (pinfunction "GND_3") (pintype "bidirectional"))
      (node (ref "C1") (pin "2") (pinfunction "2_2") (pintype "passive"))
      (node (ref "C10") (pin "2") (pinfunction "2_2") (pintype "passive"))
      (node (ref "C11") (pin "2") (pinfunction "2_2") (pintype "passive"))
      (node (ref "C12") (pin "2") (pinfunction "2_2") (pintype "passive"))
      (node (ref "C13") (pin "2") (pinfunction "2_2") (pintype "passive"))
      (node (ref "C14") (pin "2") (pinfunction "2_2") (pintype "passive"))
      (node (ref "C15") (pin "2") (pinfunction "2_2") (pintype "passive"))
      (node (ref "C16") (pin "2") (pinfunction "2_2") (pintype "passive"))
      (node (ref "C17") (pin "1") (pinfunction "1_1") (pintype "passive"))
      (node (ref "C18") (pin "2") (pinfunction "2_2") (pintype "passive"))
      (node (ref "C19") (pin "1") (pinfunction "1_1") (pintype "passive"))
      (node (ref "C2") (pin "2") (pinfunction "2_2") (pintype "passive"))
      (node (ref "C20") (pin "1") (pinfunction "1_1") (pintype "passive"))
      (node (ref "C21") (pin "1") (pinfunction "1_1") (pintype "passive"))
      (node (ref "C22") (pin "2") (pinfunction "2_2") (pintype "passive"))
      (node (ref "C25") (pin "2") (pinfunction "2_2") (pintype "passive"))
      (node (ref "C26") (pin "2") (pinfunction "2_2") (pintype "passive"))
      (node (ref "C4") (pin "2") (pinfunction "2_2") (pintype "passive"))
      (node (ref "C5") (pin "1") (pinfunction "1_1") (pintype "passive"))
      (node (ref "C51") (pin "2") (pinfunction "2_2") (pintype "passive"))
      (node (ref "C8") (pin "1") (pinfunction "1_1") (pintype "passive"))
      (node (ref "CONVERSION") (pin "4") (pinfunction "GND2_4") (pintype "passive"))
      (node (ref "C_FILTER") (pin "2") (pinfunction "2_2") (pintype "passive"))
      (node (ref "C_FILTER1") (pin "2") (pinfunction "2_2") (pintype "passive"))
      (node (ref "DC-DC_CONVERTER") (pin "6") (pinfunction "COMMON_6") (pintype "output"))
      (node (ref "FLIP-FLOP") (pin "7") (pinfunction "GND_7") (pintype "power_in"))
      (node (ref "GND1") (pin "TP") (pinfunction "TP_TP") (pintype "input"))
      (node (ref "GND2") (pin "TP") (pinfunction "TP_TP") (pintype "input"))
      (node (ref "GND3") (pin "TP") (pinfunction "TP_TP") (pintype "input"))
      (node (ref "GND5") (pin "TP") (pinfunction "TP_TP") (pintype "input"))
      (node (ref "GND_4") (pin "1") (pinfunction "1_1") (pintype "passive"))
      (node (ref "I2C") (pin "4") (pinfunction "GND1_4") (pintype "power_in"))
      (node (ref "INSTR_AMP") (pin "1") (pinfunction "-IN_1") (pintype "passive"))
      (node (ref "INSTR_AMP") (pin "2") (pinfunction "DGND_2") (pintype "bidirectional"))
      (node (ref "MINUS") (pin "1") (pinfunction "1_1") (pintype "passive"))
      (node (ref "MOV1") (pin "2") (pinfunction "2_2") (pintype "passive"))
      (node (ref "POWER1") (pin "C") (pinfunction "C_C") (pintype "passive"))
      (node (ref "R12") (pin "1") (pinfunction "1_1") (pintype "passive"))
      (node (ref "R13") (pin "1") (pinfunction "1_1") (pintype "passive"))
      (node (ref "R14") (pin "1") (pinfunction "1_1") (pintype "passive"))
      (node (ref "REF") (pin "1") (pinfunction "GND_2_1") (pintype "power_in"))
      (node (ref "REF") (pin "2") (pinfunction "GND_2") (pintype "power_in"))
      (node (ref "ROHM_I2C") (pin "1") (pinfunction "A0_1") (pintype "input"))
      (node (ref "ROHM_I2C") (pin "2") (pinfunction "A1_2") (pintype "input"))
      (node (ref "ROHM_I2C") (pin "3") (pinfunction "A2_3") (pintype "input"))
      (node (ref "ROHM_I2C") (pin "4") (pinfunction "GND_4") (pintype "passive"))
      (node (ref "SATURATION_DETECT") (pin "2") (pinfunction "GND1_2") (pintype "passive"))
      (node (ref "SERIAL_CLOCK") (pin "2") (pinfunction "GND1_2") (pintype "power_in"))
      (node (ref "SERIAL_CLOCK") (pin "5") (pinfunction "RTS_5") (pintype "passive"))
      (node (ref "SERIAL_CLOCK") (pin "6") (pinfunction "TXD_6") (pintype "passive"))
      (node (ref "SERIAL_CLOCK") (pin "8") (pinfunction "GND_1_8") (pintype "power_in"))
      (node (ref "SERIAL_DATA") (pin "2") (pinfunction "GND1_2") (pintype "power_in"))
      (node (ref "SERIAL_DATA") (pin "8") (pinfunction "GND_1_8") (pintype "power_in"))
      (node (ref "SN74LVC1G32") (pin "3") (pinfunction "GND_3") (pintype "bidirectional"))
      (node (ref "STATUS") (pin "C") (pinfunction "C_C") (pintype "passive"))
      (node (ref "TP2") (pin "TP") (pinfunction "PP_TP") (pintype "input"))
      (node (ref "TP4") (pin "TP") (pinfunction "PP_TP") (pintype "input"))
      (node (ref "U$2") (pin "1") (pinfunction "A0_1") (pintype "bidirectional"))
      (node (ref "U$2") (pin "2") (pinfunction "A1_2") (pintype "bidirectional"))
      (node (ref "U$2") (pin "3") (pinfunction "A2_3") (pintype "bidirectional"))
      (node (ref "U$2") (pin "8") (pinfunction "GND_8") (pintype "bidirectional"))
      (node (ref "U$20") (pin "2") (pinfunction "~{EN}_2") (pintype "bidirectional"))
      (node (ref "U$20") (pin "4") (pinfunction "GND_4") (pintype "bidirectional"))
      (node (ref "U$20") (pin "7") (pinfunction "NO_7") (pintype "bidirectional"))
    )
    (net (code "15") (name "GAIN_LSB") (class "Default")
      (node (ref "INSTR_AMP") (pin "4") (pinfunction "A0_4") (pintype "passive"))
      (node (ref "U$2") (pin "11") (pinfunction "P6_11") (pintype "bidirectional"))
    )
    (net (code "16") (name "GAIN_MSB") (class "Default")
      (node (ref "INSTR_AMP") (pin "5") (pinfunction "A1_5") (pintype "passive"))
      (node (ref "U$2") (pin "12") (pinfunction "P7_12") (pintype "bidirectional"))
    )
    (net (code "17") (name "INPUT_ZERO") (class "Default")
      (node (ref "U$2") (pin "9") (pinfunction "P4_9") (pintype "bidirectional"))
      (node (ref "U$20") (pin "5") (pinfunction "IN_5") (pintype "bidirectional"))
    )
    (net (code "18") (name "N_WE") (class "Default")
      (node (ref "INSTR_AMP") (pin "6") (pinfunction "~{WR}_6") (pintype "passive"))
      (node (ref "U$2") (pin "7") (pinfunction "P3_7") (pintype "bidirectional"))
    )
    (net (code "19") (name "Net-(74LVC1G11A-B)") (class "Default")
      (node (ref "74LVC1G11") (pin "3") (pinfunction "B_3") (pintype "input"))
      (node (ref "FLIP-FLOP") (pin "9") (pinfunction "2Q_9") (pintype "output"))
    )
    (net (code "20") (name "Net-(74LVC1G11A-C)") (class "Default")
      (node (ref "74LVC1G11") (pin "6") (pinfunction "C_6") (pintype "input"))
      (node (ref "FLIP-FLOP") (pin "12") (pinfunction "2D_12") (pintype "input"))
      (node (ref "FLIP-FLOP") (pin "6") (pinfunction "1~{Q}_6") (pintype "output"))
    )
    (net (code "21") (name "Net-(74LVC1G11A-Y)") (class "Default")
      (node (ref "74LVC1G11") (pin "4") (pinfunction "Y_4") (pintype "output"))
      (node (ref "SCK") (pin "3") (pinfunction "3_3") (pintype "passive"))
    )
    (net (code "22") (name "Net-(ADC_A-SCK)") (class "Default")
      (node (ref "ADC_") (pin "7") (pinfunction "SCK_7") (pintype "input"))
      (node (ref "SCK") (pin "2") (pinfunction "2_2") (pintype "passive"))
      (node (ref "SCK_A") (pin "TP") (pinfunction "TP_TP") (pintype "input"))
    )
    (net (code "23") (name "Net-(ADC_B-REF)") (class "Default")
      (node (ref "ADC_") (pin "2") (pinfunction "REF_2") (pintype "bidirectional"))
      (node (ref "ADC_REF") (pin "1") (pinfunction "1_1") (pintype "passive"))
      (node (ref "C19") (pin "2") (pinfunction "2_2") (pintype "passive"))
    )
    (net (code "24") (name "Net-(CONVERSIONA-VOUT)") (class "Default")
      (node (ref "CONV") (pin "2") (pinfunction "2_2") (pintype "passive"))
      (node (ref "CONVERSION") (pin "5") (pinfunction "VOUT_5") (pintype "output"))
      (node (ref "CONV_T") (pin "TP") (pinfunction "TP_TP") (pintype "input"))
    )
    (net (code "25") (name "Net-(DC-DC_CONVERTER-+VIN(VCC))") (class "Default")
      (node (ref "DC-DC_CONVERTER") (pin "1") (pinfunction "+VIN(VCC)_1") (pintype "power_in"))
      (node (ref "L1") (pin "1") (pinfunction "1_1") (pintype "passive"))
    )
    (net (code "26") (name "Net-(DC-DC_CONVERTER-ON{slash}OFF)") (class "Default")
      (node (ref "DC-DC_CONVERTER") (pin "4") (pinfunction "ON/OFF_4") (pintype "bidirectional"))
      (node (ref "ON/OFF") (pin "2") (pinfunction "2_2") (pintype "passive"))
    )
    (net (code "27") (name "Net-(FLIP-FLOPA-1D)") (class "Default")
      (node (ref "CONV") (pin "3") (pinfunction "3_3") (pintype "passive"))
      (node (ref "FLIP-FLOP") (pin "2") (pinfunction "1D_2") (pintype "input"))
    )
    (net (code "28") (name "Net-(I2CA-SCL1)") (class "Default")
      (node (ref "I2C") (pin "3") (pinfunction "SCL1_3") (pintype "bidirectional"))
      (node (ref "R18") (pin "1") (pinfunction "1_1") (pintype "passive"))
      (node (ref "ROHM_I2C") (pin "6") (pinfunction "SCL_6") (pintype "input"))
      (node (ref "U$2") (pin "14") (pinfunction "SCL_14") (pintype "bidirectional"))
    )
    (net (code "29") (name "Net-(I2CA-SDA1)") (class "Default")
      (node (ref "I2C") (pin "2") (pinfunction "SDA1_2") (pintype "bidirectional"))
      (node (ref "R19") (pin "1") (pinfunction "1_1") (pintype "passive"))
      (node (ref "ROHM_I2C") (pin "5") (pinfunction "SDA_5") (pintype "bidirectional"))
      (node (ref "U$2") (pin "15") (pinfunction "SDA_15") (pintype "bidirectional"))
    )
    (net (code "30") (name "Net-(INSTR_AMPA-+IN)") (class "Default")
      (node (ref "C_FILTER1") (pin "1") (pinfunction "1_1") (pintype "passive"))
      (node (ref "INSTR_AMP") (pin "10") (pinfunction "+IN_10") (pintype "passive"))
      (node (ref "R_FILTER1") (pin "1") (pinfunction "1_1") (pintype "passive"))
    )
    (net (code "31") (name "Net-(INSTR_AMPA-OUT)") (class "Default")
      (node (ref "INSTR_AMP") (pin "7") (pinfunction "OUT_7") (pintype "passive"))
      (node (ref "R_FILTER") (pin "2") (pinfunction "2_2") (pintype "passive"))
    )
    (net (code "32") (name "Net-(LED2-PadC)") (class "Default")
      (node (ref "LED2") (pin "C") (pinfunction "C_C") (pintype "passive"))
      (node (ref "R3") (pin "2") (pinfunction "2_2") (pintype "passive"))
    )
    (net (code "33") (name "Net-(ON/OFF-Pad3)") (class "Default")
      (node (ref "ON/OFF") (pin "3") (pinfunction "3_3") (pintype "passive"))
      (node (ref "R2") (pin "2") (pinfunction "2_2") (pintype "passive"))
    )
    (net (code "34") (name "Net-(POWER-PadA)") (class "Default")
      (node (ref "POWER") (pin "A") (pinfunction "A_A") (pintype "passive"))
      (node (ref "R21") (pin "1") (pinfunction "1_1") (pintype "passive"))
    )
    (net (code "35") (name "Net-(POWER1-PadA)") (class "Default")
      (node (ref "POWER1") (pin "A") (pinfunction "A_A") (pintype "passive"))
      (node (ref "R23") (pin "1") (pinfunction "1_1") (pintype "passive"))
    )
    (net (code "36") (name "Net-(R4-Pad2)") (class "Default")
      (node (ref "R4") (pin "2") (pinfunction "2_2") (pintype "passive"))
      (node (ref "R53") (pin "1") (pinfunction "1_1") (pintype "passive"))
    )
    (net (code "37") (name "Net-(R5-Pad1)") (class "Default")
      (node (ref "R5") (pin "1") (pinfunction "1_1") (pintype "passive"))
      (node (ref "R57") (pin "2") (pinfunction "2_2") (pintype "passive"))
    )
    (net (code "38") (name "Net-(R8-Pad1)") (class "Default")
      (node (ref "R8") (pin "1") (pinfunction "1_1") (pintype "passive"))
      (node (ref "STATUS") (pin "A") (pinfunction "A_A") (pintype "passive"))
    )
    (net (code "39") (name "Net-(R53-Pad2)") (class "Default")
      (node (ref "R53") (pin "2") (pinfunction "2_2") (pintype "passive"))
      (node (ref "R58") (pin "1") (pinfunction "1_1") (pintype "passive"))
    )
    (net (code "40") (name "Net-(R57-Pad1)") (class "Default")
      (node (ref "R57") (pin "1") (pinfunction "1_1") (pintype "passive"))
      (node (ref "R58") (pin "2") (pinfunction "2_2") (pintype "passive"))
    )
    (net (code "41") (name "Net-(SATURATION_DETECTA-INA+)") (class "Default")
      (node (ref "R11") (pin "1") (pinfunction "1_1") (pintype "passive"))
      (node (ref "R13") (pin "2") (pinfunction "2_2") (pintype "passive"))
      (node (ref "SATURATION_DETECT") (pin "3") (pinfunction "INA+_3") (pintype "input"))
    )
    (net (code "42") (name "Net-(SATURATION_DETECTA-INB-)") (class "Default")
      (node (ref "R10") (pin "1") (pinfunction "1_1") (pintype "passive"))
      (node (ref "R12") (pin "2") (pinfunction "2_2") (pintype "passive"))
      (node (ref "SATURATION_DETECT") (pin "4") (pinfunction "INB-_4") (pintype "input"))
    )
    (net (code "43") (name "Net-(SERIAL_CLOCKA-DE)") (class "Default")
      (node (ref "DE_CLK") (pin "1") (pinfunction "1_1") (pintype "passive"))
      (node (ref "SERIAL_CLOCK") (pin "10") (pinfunction "DE_10") (pintype "passive"))
    )
    (net (code "44") (name "Net-(SERIAL_DATAA-DE)") (class "Default")
      (node (ref "DE_DATA") (pin "1") (pinfunction "1_1") (pintype "passive"))
      (node (ref "SERIAL_DATA") (pin "10") (pinfunction "DE_10") (pintype "passive"))
    )
    (net (code "45") (name "Net-(SERIAL_DATAA-TXD)") (class "Default")
      (node (ref "SDO") (pin "2") (pinfunction "2_2") (pintype "passive"))
      (node (ref "SDO_T") (pin "TP") (pinfunction "TP_TP") (pintype "input"))
      (node (ref "SERIAL_DATA") (pin "6") (pinfunction "TXD_6") (pintype "passive"))
    )
    (net (code "46") (name "Net-(SN74LVC1G32A-Y)") (class "Default")
      (node (ref "SDO") (pin "3") (pinfunction "3_3") (pintype "passive"))
      (node (ref "SN74LVC1G32") (pin "4") (pinfunction "Y_4") (pintype "output"))
    )
    (net (code "47") (name "Net-(TP1-PP)") (class "Default")
      (node (ref "PLUS") (pin "1") (pinfunction "1_1") (pintype "passive"))
      (node (ref "TP1") (pin "TP") (pinfunction "PP_TP") (pintype "input"))
      (node (ref "TP3") (pin "TP") (pinfunction "PP_TP") (pintype "input"))
      (node (ref "U$1") (pin "P$1") (pinfunction "IN_P$1") (pintype "bidirectional"))
    )
    (net (code "48") (name "Net-(U$1-OUT)") (class "Default")
      (node (ref "MOV1") (pin "1") (pinfunction "1_1") (pintype "passive"))
      (node (ref "R5") (pin "2") (pinfunction "2_2") (pintype "passive"))
      (node (ref "U$1") (pin "P$2") (pinfunction "OUT_P$2") (pintype "bidirectional"))
    )
    (net (code "49") (name "Net-(U$2-N_INT)") (class "Default")
      (node (ref "R1") (pin "2") (pinfunction "2_2") (pintype "passive"))
      (node (ref "U$2") (pin "13") (pinfunction "N_INT_13") (pintype "bidirectional"))
    )
    (net (code "50") (name "Net-(U$20A-COM)") (class "Default")
      (node (ref "FILTER") (pin "1") (pinfunction "1_1") (pintype "passive"))
      (node (ref "R_FILTER1") (pin "2") (pinfunction "2_2") (pintype "passive"))
      (node (ref "U$20") (pin "1") (pinfunction "COM_1") (pintype "bidirectional"))
    )
    (net (code "51") (name "Net-(U$20A-NC)") (class "Default")
      (node (ref "ANALOG_IN") (pin "TP") (pinfunction "TP_TP") (pintype "input"))
      (node (ref "A_IN") (pin "1") (pinfunction "1_1") (pintype "passive"))
      (node (ref "R14") (pin "2") (pinfunction "2_2") (pintype "passive"))
      (node (ref "R4") (pin "1") (pinfunction "1_1") (pintype "passive"))
      (node (ref "U$20") (pin "6") (pinfunction "NC_6") (pintype "bidirectional"))
    )
    (net (code "52") (name "SAT_DETECT") (class "Default")
      (node (ref "R3") (pin "1") (pinfunction "1_1") (pintype "passive"))
      (node (ref "SATURATION_DETECT") (pin "1") (pinfunction "OUTA_1") (pintype "output"))
      (node (ref "SATURATION_DETECT") (pin "6") (pinfunction "OUTB_6") (pintype "output"))
      (node (ref "U$2") (pin "10") (pinfunction "P5_10") (pintype "bidirectional"))
    )
    (net (code "53") (name "SCK_ADC") (class "Default")
      (node (ref "74LVC1G11") (pin "1") (pinfunction "A_1") (pintype "input"))
      (node (ref "FLIP-FLOP") (pin "11") (pinfunction "2CP_11") (pintype "input"))
      (node (ref "FLIP-FLOP") (pin "3") (pinfunction "1CP_3") (pintype "input"))
      (node (ref "SCK") (pin "1") (pinfunction "1_1") (pintype "passive"))
      (node (ref "SCK_T") (pin "TP") (pinfunction "TP_TP") (pintype "input"))
      (node (ref "SERIAL_CLOCK") (pin "3") (pinfunction "RXD_3") (pintype "passive"))
    )
    (net (code "54") (name "SCL") (class "Default")
      (node (ref "I2C") (pin "6") (pinfunction "SCL2_6") (pintype "bidirectional"))
      (node (ref "R22") (pin "1") (pinfunction "1_1") (pintype "passive"))
      (node (ref "RJ45") (pin "7") (pinfunction "7_7") (pintype "passive"))
    )
    (net (code "55") (name "SDO") (class "Default")
      (node (ref "I2C") (pin "7") (pinfunction "SDA2_7") (pintype "bidirectional"))
      (node (ref "R20") (pin "1") (pinfunction "1_1") (pintype "passive"))
      (node (ref "RJ45") (pin "8") (pinfunction "8_8") (pintype "passive"))
    )
    (net (code "56") (name "SDO_ADC") (class "Default")
      (node (ref "ADC_") (pin "6") (pinfunction "SDO_6") (pintype "output"))
      (node (ref "SDO") (pin "1") (pinfunction "1_1") (pintype "passive"))
      (node (ref "SDO_A") (pin "TP") (pinfunction "TP_TP") (pintype "input"))
      (node (ref "SN74LVC1G32") (pin "2") (pinfunction "B_2") (pintype "input"))
    )
    (net (code "57") (name "STATUS_LED") (class "Default")
      (node (ref "R8") (pin "2") (pinfunction "2_2") (pintype "passive"))
      (node (ref "U$2") (pin "6") (pinfunction "P2_6") (pintype "bidirectional"))
    )
    (net (code "58") (name "VCC") (class "Default")
      (node (ref "C23") (pin "2") (pinfunction "2_2") (pintype "passive"))
      (node (ref "C3") (pin "1") (pinfunction "1_1") (pintype "passive"))
      (node (ref "C6") (pin "1") (pinfunction "1_1") (pintype "passive"))
      (node (ref "C7") (pin "1") (pinfunction "1_1") (pintype "passive"))
      (node (ref "C9") (pin "1") (pinfunction "1_1") (pintype "passive"))
      (node (ref "CONVERSION") (pin "1") (pinfunction "VDD1_1") (pintype "passive"))
      (node (ref "I2C") (pin "8") (pinfunction "VDD2_8") (pintype "passive"))
      (node (ref "L1") (pin "2") (pinfunction "2_2") (pintype "passive"))
      (node (ref "R16") (pin "1") (pinfunction "1_1") (pintype "passive"))
      (node (ref "R2") (pin "1") (pinfunction "1_1") (pintype "passive"))
      (node (ref "R20") (pin "2") (pinfunction "2_2") (pintype "passive"))
      (node (ref "R21") (pin "2") (pinfunction "2_2") (pintype "passive"))
      (node (ref "R22") (pin "2") (pinfunction "2_2") (pintype "passive"))
      (node (ref "R6") (pin "1") (pinfunction "1_1") (pintype "passive"))
      (node (ref "RJ45") (pin "4") (pinfunction "4_4") (pintype "passive"))
      (node (ref "SERIAL_CLOCK") (pin "16") (pinfunction "VDD2_16") (pintype "power_in"))
      (node (ref "SERIAL_DATA") (pin "16") (pinfunction "VDD2_16") (pintype "power_in"))
      (node (ref "VCC") (pin "1") (pinfunction "1_1") (pintype "passive"))
    )
    (net (code "59") (name "unconnected-(FLIP-FLOPA-2~{Q}-Pad8)") (class "Default")
      (node (ref "FLIP-FLOP") (pin "8") (pinfunction "2~{Q}_8") (pintype "output"))
    )
    (net (code "60") (name "unconnected-(ON/OFF-Pad1)") (class "Default")
      (node (ref "ON/OFF") (pin "1") (pinfunction "1_1") (pintype "passive"))
    )
    (net (code "61") (name "unconnected-(REF-DNC-Pad3)") (class "Default")
      (node (ref "REF") (pin "3") (pinfunction "DNC_3") (pintype "no_connect"))
    )
    (net (code "62") (name "unconnected-(REF-DNC_2-Pad5)") (class "Default")
      (node (ref "REF") (pin "5") (pinfunction "DNC_2_5") (pintype "no_connect"))
    )
    (net (code "63") (name "unconnected-(SERIAL_DATAA-RXD-Pad3)") (class "Default")
      (node (ref "SERIAL_DATA") (pin "3") (pinfunction "RXD_3") (pintype "passive"))
    )
  )
)
